# VHF_AMP.net
KiCad netlist of a schematic drawn in Altium Designer
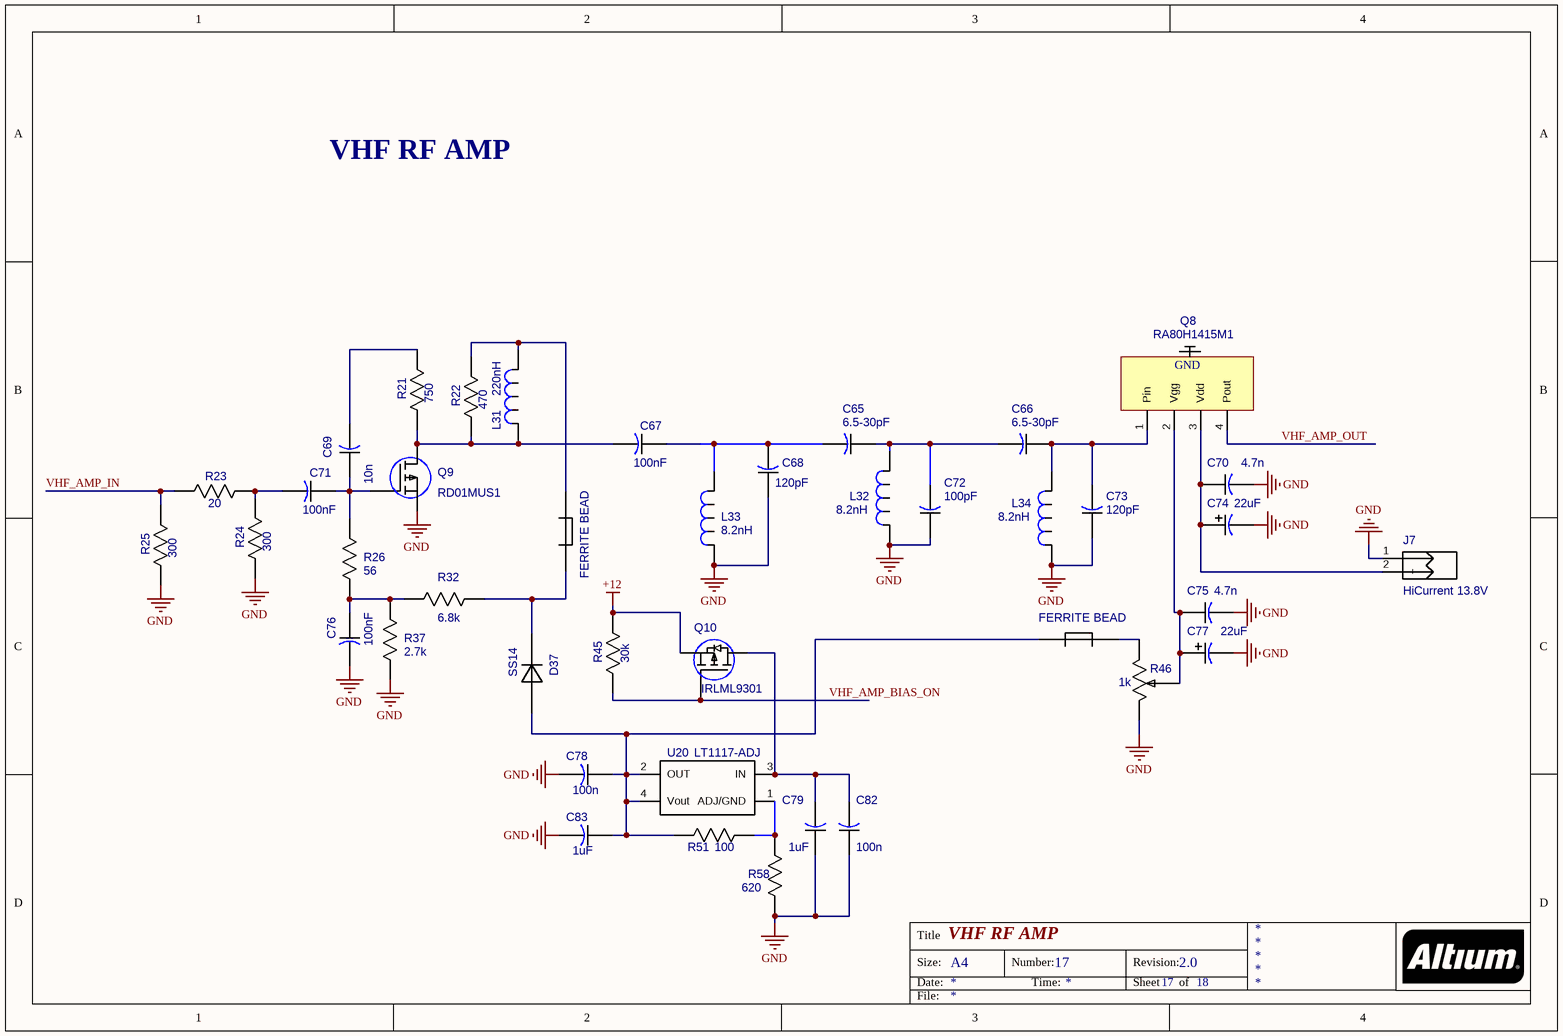
[diagram p0: VHF_AMP.SchDoc]

(export (version "E")
  (design (tool "Eeschema 10.0.6"))
  (components
    (comp (ref "C65")
      (value "6.5-30pF")
      (footprint "5025[2010]")
      (description "TZC3P300A110")
      (libsource (lib "*") (part "CAP_0805"))
    )
    (comp (ref "C66")
      (value "6.5-30pF")
      (footprint "5025[2010]")
      (description "TZC3P300A110")
      (libsource (lib "*") (part "CAP_0805"))
    )
    (comp (ref "C67")
      (value "100nF")
      (footprint "CAP_0805")
      (description "CAP_0805")
      (libsource (lib "*") (part "CAP_0805"))
    )
    (comp (ref "C68")
      (value "120pF")
      (footprint "CAP_0805")
      (description "CAP_0805")
      (libsource (lib "*") (part "CAP_0805"))
    )
    (comp (ref "C69")
      (value "10n")
      (footprint "CAP_1206")
      (description "CAP_1206")
      (libsource (lib "*") (part "CAP_1206"))
    )
    (comp (ref "C70")
      (value "4.7n")
      (footprint "CAP_0805")
      (description "CAP_0805")
      (libsource (lib "*") (part "CAP_0805"))
    )
    (comp (ref "C71")
      (value "100nF")
      (footprint "CAP_0805")
      (description "CAP_0805")
      (libsource (lib "*") (part "CAP_0805"))
    )
    (comp (ref "C72")
      (value "100pF")
      (footprint "CAP_0805")
      (description "CAP_0805")
      (libsource (lib "*") (part "CAP_0805"))
    )
    (comp (ref "C73")
      (value "120pF")
      (footprint "CAP_0805")
      (description "CAP_0805")
      (libsource (lib "*") (part "CAP_0805"))
    )
    (comp (ref "C74")
      (value "22uF")
      (footprint "CAPAE_6.6x6.6h5.4")
      (description "CAPAE_6.6x6.6h5.4")
      (libsource (lib "*") (part "CAPAE_6.6x6.6h5.4"))
    )
    (comp (ref "C75")
      (value "4.7n")
      (footprint "CAP_0805")
      (description "CAP_0805")
      (libsource (lib "*") (part "CAP_0805"))
    )
    (comp (ref "C76")
      (value "100nF")
      (footprint "CAP_0805")
      (description "CAP_0805")
      (libsource (lib "*") (part "CAP_0805"))
    )
    (comp (ref "C77")
      (value "22uF")
      (footprint "CAPAE_6.6x6.6h5.4")
      (description "CAPAE_6.6x6.6h5.4")
      (libsource (lib "*") (part "CAPAE_6.6x6.6h5.4"))
    )
    (comp (ref "C78")
      (value "100n")
      (footprint "CAP_0805")
      (description "CAP_0805")
      (libsource (lib "*") (part "CAP_0805"))
    )
    (comp (ref "C79")
      (value "1uF")
      (footprint "CAP_0805")
      (description "CAP_0805")
      (libsource (lib "*") (part "CAP_0805"))
    )
    (comp (ref "C82")
      (value "100n")
      (footprint "CAP_0805")
      (description "CAP_0805")
      (libsource (lib "*") (part "CAP_0805"))
    )
    (comp (ref "C83")
      (value "1uF")
      (footprint "CAP_0805")
      (description "CAP_0805")
      (libsource (lib "*") (part "CAP_0805"))
    )
    (comp (ref "D37") (value "SS14") (footprint "SS14") (libsource (lib "*") (part "SS14")))
    (comp (ref "F1")
      (value "FERRITE BEAD")
      (footprint "RES")
      (description "IND_FERRITE_BEAD")
      (libsource (lib "RF-UNIT-BIG") (part "IND_FERRITE_BEAD"))
    )
    (comp (ref "F2")
      (value "FERRITE BEAD")
      (footprint "RES")
      (description "IND_FERRITE_BEAD")
      (libsource (lib "RF-UNIT-BIG") (part "IND_FERRITE_BEAD"))
    )
    (comp (ref "J7")
      (value "HiCurrent 13.8V")
      (footprint "1986717-2")
      (description "JX2")
      (libsource (lib "*") (part "1986717-2"))
    )
    (comp (ref "L31")
      (value "220nH")
      (footprint "IND_1206")
      (description "IND_1206")
      (fields (field (name "Comment") "10uH"))
      (libsource (lib "*") (part "IND_1206"))
    )
    (comp (ref "L32")
      (value "8.2nH")
      (footprint "IND_0805")
      (description "IND_0805")
      (libsource (lib "*") (part "IND_0805"))
    )
    (comp (ref "L33")
      (value "8.2nH")
      (footprint "IND_0805")
      (description "IND_0805")
      (libsource (lib "*") (part "IND_0805"))
    )
    (comp (ref "L34")
      (value "8.2nH")
      (footprint "IND_0805")
      (description "IND_0805")
      (libsource (lib "*") (part "IND_0805"))
    )
    (comp (ref "Q8")
      (value "RA80H1415M1")
      (footprint "RA80H1415M1")
      (libsource (lib "RF-UNIT-BIG") (part "RA80H1415M1"))
    )
    (comp (ref "Q9") (value "RD01MUS1") (footprint "SOT89") (libsource (lib "RF-UNIT-BIG") (part "RD01MUS1")))
    (comp (ref "Q10")
      (value "IRLML9301")
      (footprint "SOT23")
      (description "MOSFET")
      (libsource (lib "*") (part "MOSFET_ENH_PD"))
    )
    (comp (ref "R21")
      (value "750")
      (footprint "RES_1206")
      (description "RES_1206")
      (libsource (lib "*") (part "RES_1206"))
    )
    (comp (ref "R22")
      (value "470")
      (footprint "RES_1206")
      (description "RES_1206")
      (libsource (lib "*") (part "RES_1206"))
    )
    (comp (ref "R23")
      (value "20")
      (footprint "RES_1206")
      (description "RES_1206")
      (libsource (lib "*") (part "RES_1206"))
    )
    (comp (ref "R24")
      (value "300")
      (footprint "RES_1206")
      (description "RES_1206")
      (libsource (lib "*") (part "RES_1206"))
    )
    (comp (ref "R25")
      (value "300")
      (footprint "RES_1206")
      (description "RES_1206")
      (libsource (lib "*") (part "RES_1206"))
    )
    (comp (ref "R26")
      (value "56")
      (footprint "RES_0805")
      (description "RES_0805")
      (libsource (lib "*") (part "RES_0805"))
    )
    (comp (ref "R32")
      (value "6.8k")
      (footprint "RES_0805")
      (description "RES_0805")
      (libsource (lib "*") (part "RES_0805"))
    )
    (comp (ref "R37")
      (value "2.7k")
      (footprint "RES_0805")
      (description "RES_0805")
      (libsource (lib "*") (part "RES_0805"))
    )
    (comp (ref "R45")
      (value "30k")
      (footprint "RES_0805")
      (description "RES_0805")
      (libsource (lib "*") (part "RES_0805"))
    )
    (comp (ref "R46")
      (value "1k")
      (footprint "306J")
      (description "306J")
      (fields (field (name "Comment") "ADJ-1k"))
      (libsource (lib "*") (part "306J"))
    )
    (comp (ref "R51")
      (value "100")
      (footprint "RES_0805")
      (description "RES_0805")
      (libsource (lib "*") (part "RES_0805"))
    )
    (comp (ref "R58")
      (value "620")
      (footprint "RES_0805")
      (description "RES_0805")
      (libsource (lib "*") (part "RES_0805"))
    )
    (comp (ref "U20")
      (value "LT1117-ADJ")
      (footprint "LT1117IST-ADJ")
      (description "LT1117IST-ADJ")
      (libsource (lib "*") (part "LT1117IST-ADJ"))
    )
  )
  (nets
    (net (code "1") (name "+12") (class "Default")
      (node (ref "Q10") (pin "2") (pinfunction "S_2") (pintype "passive"))
      (node (ref "R45") (pin "2") (pinfunction "2_2") (pintype "passive"))
    )
    (net (code "2") (name "/VHF_AMP_BIAS_ON") (class "Default")
      (node (ref "Q10") (pin "1") (pinfunction "G_1") (pintype "passive"))
      (node (ref "R45") (pin "1") (pinfunction "1_1") (pintype "passive"))
    )
    (net (code "3") (name "/VHF_AMP_IN") (class "Default")
      (node (ref "R23") (pin "1") (pinfunction "1_1") (pintype "passive"))
      (node (ref "R25") (pin "2") (pinfunction "2_2") (pintype "passive"))
    )
    (net (code "4") (name "/VHF_AMP_OUT") (class "Default")
      (node (ref "Q8") (pin "4") (pinfunction "Pout_4") (pintype "passive"))
    )
    (net (code "5") (name "GND") (class "Default")
      (node (ref "C68") (pin "1") (pinfunction "1_1") (pintype "passive"))
      (node (ref "C70") (pin "2") (pinfunction "2_2") (pintype "passive"))
      (node (ref "C72") (pin "1") (pinfunction "1_1") (pintype "passive"))
      (node (ref "C73") (pin "1") (pinfunction "1_1") (pintype "passive"))
      (node (ref "C74") (pin "2") (pinfunction "MINUS_2") (pintype "passive"))
      (node (ref "C75") (pin "2") (pinfunction "2_2") (pintype "passive"))
      (node (ref "C76") (pin "2") (pinfunction "2_2") (pintype "passive"))
      (node (ref "C77") (pin "2") (pinfunction "MINUS_2") (pintype "passive"))
      (node (ref "C78") (pin "2") (pinfunction "2_2") (pintype "passive"))
      (node (ref "C79") (pin "1") (pinfunction "1_1") (pintype "passive"))
      (node (ref "C82") (pin "1") (pinfunction "1_1") (pintype "passive"))
      (node (ref "C83") (pin "2") (pinfunction "2_2") (pintype "passive"))
      (node (ref "J7") (pin "1") (pinfunction "-_1") (pintype "passive"))
      (node (ref "L32") (pin "1") (pinfunction "1_1") (pintype "passive"))
      (node (ref "L33") (pin "1") (pinfunction "1_1") (pintype "passive"))
      (node (ref "L34") (pin "1") (pinfunction "1_1") (pintype "passive"))
      (node (ref "Q9") (pin "2") (pinfunction "S_2") (pintype "passive"))
      (node (ref "R24") (pin "1") (pinfunction "1_1") (pintype "passive"))
      (node (ref "R25") (pin "1") (pinfunction "1_1") (pintype "passive"))
      (node (ref "R37") (pin "1") (pinfunction "1_1") (pintype "passive"))
      (node (ref "R46") (pin "1") (pinfunction "CCW_1") (pintype "passive"))
      (node (ref "R58") (pin "2") (pinfunction "2_2") (pintype "passive"))
    )
    (net (code "6") (name "Net-(C65-Pad1)") (class "Default")
      (node (ref "C65") (pin "1") (pinfunction "1_1") (pintype "passive"))
      (node (ref "C66") (pin "2") (pinfunction "2_2") (pintype "passive"))
      (node (ref "C72") (pin "2") (pinfunction "2_2") (pintype "passive"))
      (node (ref "L32") (pin "2") (pinfunction "2_2") (pintype "passive"))
    )
    (net (code "7") (name "Net-(C65-Pad2)") (class "Default")
      (node (ref "C65") (pin "2") (pinfunction "2_2") (pintype "passive"))
      (node (ref "C67") (pin "1") (pinfunction "1_1") (pintype "passive"))
      (node (ref "C68") (pin "2") (pinfunction "2_2") (pintype "passive"))
      (node (ref "L33") (pin "2") (pinfunction "2_2") (pintype "passive"))
    )
    (net (code "8") (name "Net-(C69-Pad2)") (class "Default")
      (node (ref "C69") (pin "2") (pinfunction "2_2") (pintype "passive"))
      (node (ref "R21") (pin "2") (pinfunction "2_2") (pintype "passive"))
    )
    (net (code "9") (name "Net-(C71-Pad2)") (class "Default")
      (node (ref "C71") (pin "2") (pinfunction "2_2") (pintype "passive"))
      (node (ref "R23") (pin "2") (pinfunction "2_2") (pintype "passive"))
      (node (ref "R24") (pin "2") (pinfunction "2_2") (pintype "passive"))
    )
    (net (code "10") (name "Net-(C74-PLUS)") (class "Default")
      (node (ref "C70") (pin "1") (pinfunction "1_1") (pintype "passive"))
      (node (ref "C74") (pin "1") (pinfunction "PLUS_1") (pintype "passive"))
      (node (ref "J7") (pin "2") (pinfunction "+_2") (pintype "passive"))
      (node (ref "Q8") (pin "3") (pinfunction "Vdd_3") (pintype "passive"))
    )
    (net (code "11") (name "Net-(C76-Pad1)") (class "Default")
      (node (ref "C76") (pin "1") (pinfunction "1_1") (pintype "passive"))
      (node (ref "R26") (pin "1") (pinfunction "1_1") (pintype "passive"))
      (node (ref "R32") (pin "2") (pinfunction "2_2") (pintype "passive"))
      (node (ref "R37") (pin "2") (pinfunction "2_2") (pintype "passive"))
    )
    (net (code "12") (name "Net-(C77-PLUS)") (class "Default")
      (node (ref "C75") (pin "1") (pinfunction "1_1") (pintype "passive"))
      (node (ref "C77") (pin "1") (pinfunction "PLUS_1") (pintype "passive"))
      (node (ref "Q8") (pin "2") (pinfunction "Vgg_2") (pintype "passive"))
      (node (ref "R46") (pin "2") (pinfunction "W_2") (pintype "passive"))
    )
    (net (code "13") (name "Net-(D37-A)") (class "Default")
      (node (ref "C78") (pin "1") (pinfunction "1_1") (pintype "passive"))
      (node (ref "C83") (pin "1") (pinfunction "1_1") (pintype "passive"))
      (node (ref "D37") (pin "2") (pinfunction "A_2") (pintype "passive"))
      (node (ref "F2") (pin "1") (pinfunction "1_1") (pintype "passive"))
      (node (ref "R51") (pin "1") (pinfunction "1_1") (pintype "passive"))
      (node (ref "U20") (pin "2") (pinfunction "OUT_2") (pintype "passive"))
      (node (ref "U20") (pin "4") (pinfunction "Vout_4") (pintype "passive"))
    )
    (net (code "14") (name "Net-(D37-K)") (class "Default")
      (node (ref "D37") (pin "1") (pinfunction "K_1") (pintype "passive"))
      (node (ref "F1") (pin "2") (pinfunction "2_2") (pintype "passive"))
      (node (ref "R32") (pin "1") (pinfunction "1_1") (pintype "passive"))
    )
    (net (code "15") (name "Net-(L31-1)") (class "Default")
      (node (ref "C67") (pin "2") (pinfunction "2_2") (pintype "passive"))
      (node (ref "L31") (pin "2") (pinfunction "1_2") (pintype "passive"))
      (node (ref "Q9") (pin "3") (pinfunction "D_3") (pintype "passive"))
      (node (ref "R21") (pin "1") (pinfunction "1_1") (pintype "passive"))
      (node (ref "R22") (pin "1") (pinfunction "1_1") (pintype "passive"))
    )
    (net (code "16") (name "Net-(L31-2)") (class "Default")
      (node (ref "F1") (pin "1") (pinfunction "1_1") (pintype "passive"))
      (node (ref "L31") (pin "1") (pinfunction "2_1") (pintype "passive"))
      (node (ref "R22") (pin "2") (pinfunction "2_2") (pintype "passive"))
    )
    (net (code "17") (name "Net-(Q8-Pin)") (class "Default")
      (node (ref "C66") (pin "1") (pinfunction "1_1") (pintype "passive"))
      (node (ref "C73") (pin "2") (pinfunction "2_2") (pintype "passive"))
      (node (ref "L34") (pin "2") (pinfunction "2_2") (pintype "passive"))
      (node (ref "Q8") (pin "1") (pinfunction "Pin_1") (pintype "passive"))
    )
    (net (code "18") (name "Net-(Q9-G)") (class "Default")
      (node (ref "C69") (pin "1") (pinfunction "1_1") (pintype "passive"))
      (node (ref "C71") (pin "1") (pinfunction "1_1") (pintype "passive"))
      (node (ref "Q9") (pin "1") (pinfunction "G_1") (pintype "passive"))
      (node (ref "R26") (pin "2") (pinfunction "2_2") (pintype "passive"))
    )
    (net (code "19") (name "Net-(Q10-D)") (class "Default")
      (node (ref "C79") (pin "2") (pinfunction "2_2") (pintype "passive"))
      (node (ref "C82") (pin "2") (pinfunction "2_2") (pintype "passive"))
      (node (ref "Q10") (pin "3") (pinfunction "D_3") (pintype "passive"))
      (node (ref "U20") (pin "3") (pinfunction "IN_3") (pintype "passive"))
    )
    (net (code "20") (name "Net-(R46-CW)") (class "Default")
      (node (ref "F2") (pin "2") (pinfunction "2_2") (pintype "passive"))
      (node (ref "R46") (pin "3") (pinfunction "CW_3") (pintype "passive"))
    )
    (net (code "21") (name "Net-(U20-ADJ{slash}GND)") (class "Default")
      (node (ref "R51") (pin "2") (pinfunction "2_2") (pintype "passive"))
      (node (ref "R58") (pin "1") (pinfunction "1_1") (pintype "passive"))
      (node (ref "U20") (pin "1") (pinfunction "ADJ/GND_1") (pintype "passive"))
    )
  )
)
